# TG21_TX_Xu_ly_ma_tran_phim.net
KiCad netlist of a schematic drawn in Altium Designer
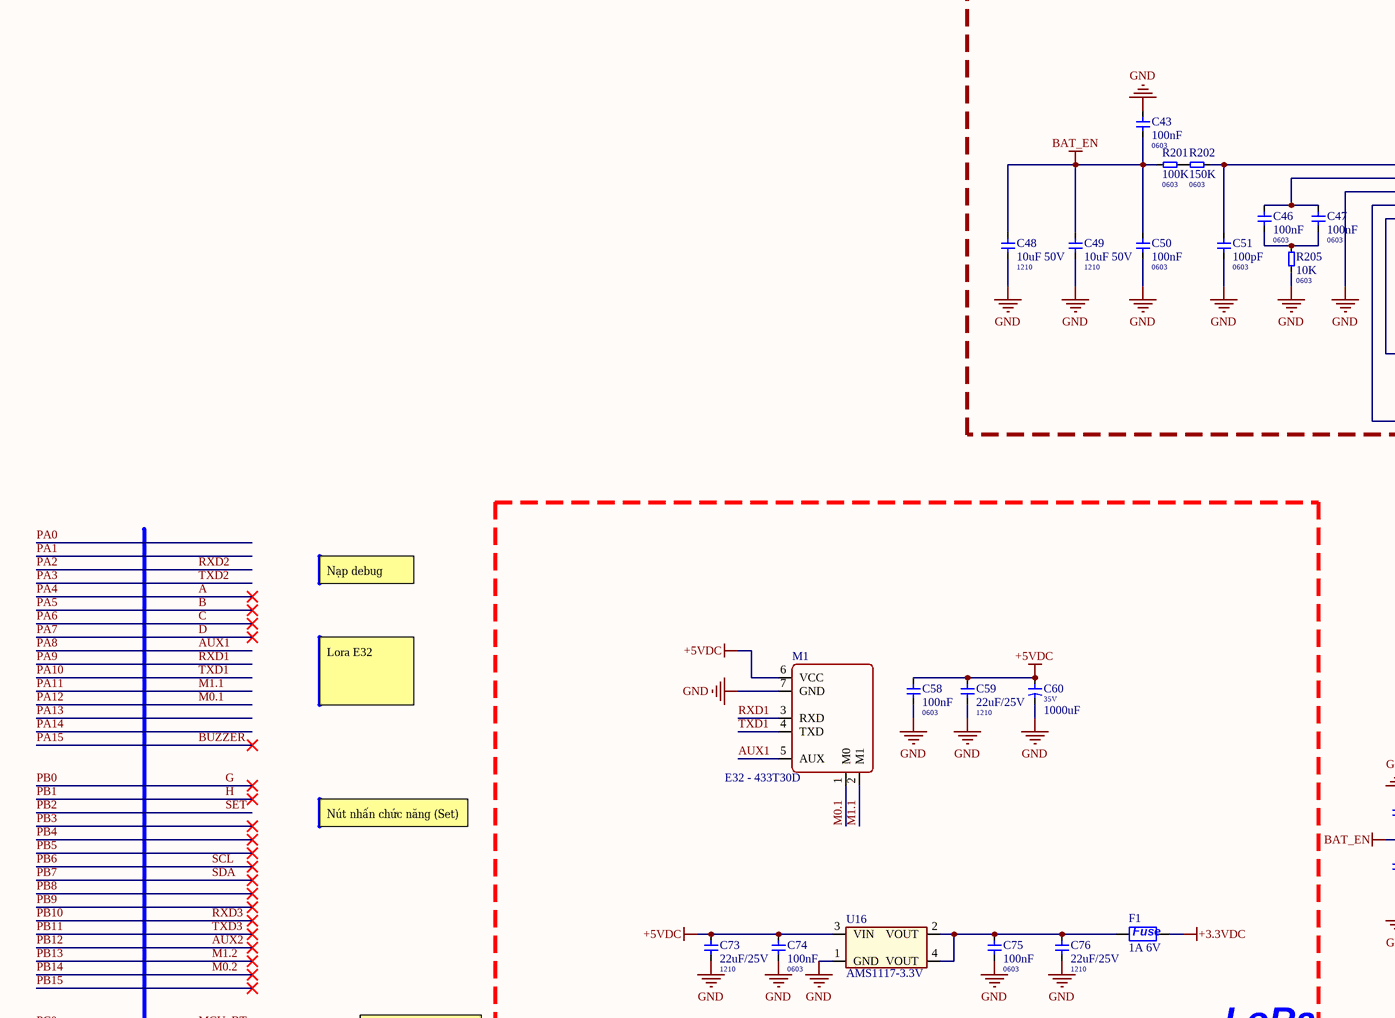
[diagram p0: TG21_TX_Xu ly ma tran phim.SchDoc, top left]
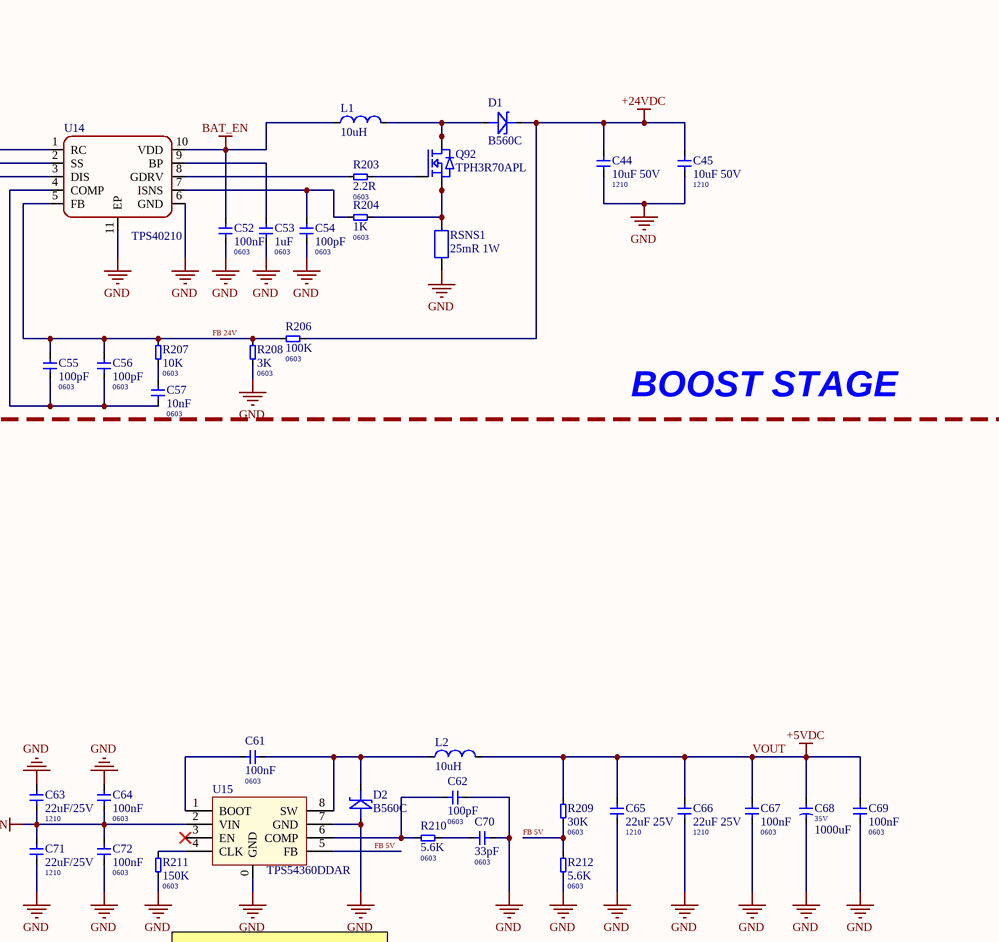
[diagram p1: TG21_TX_Xu ly ma tran phim.SchDoc, top right]
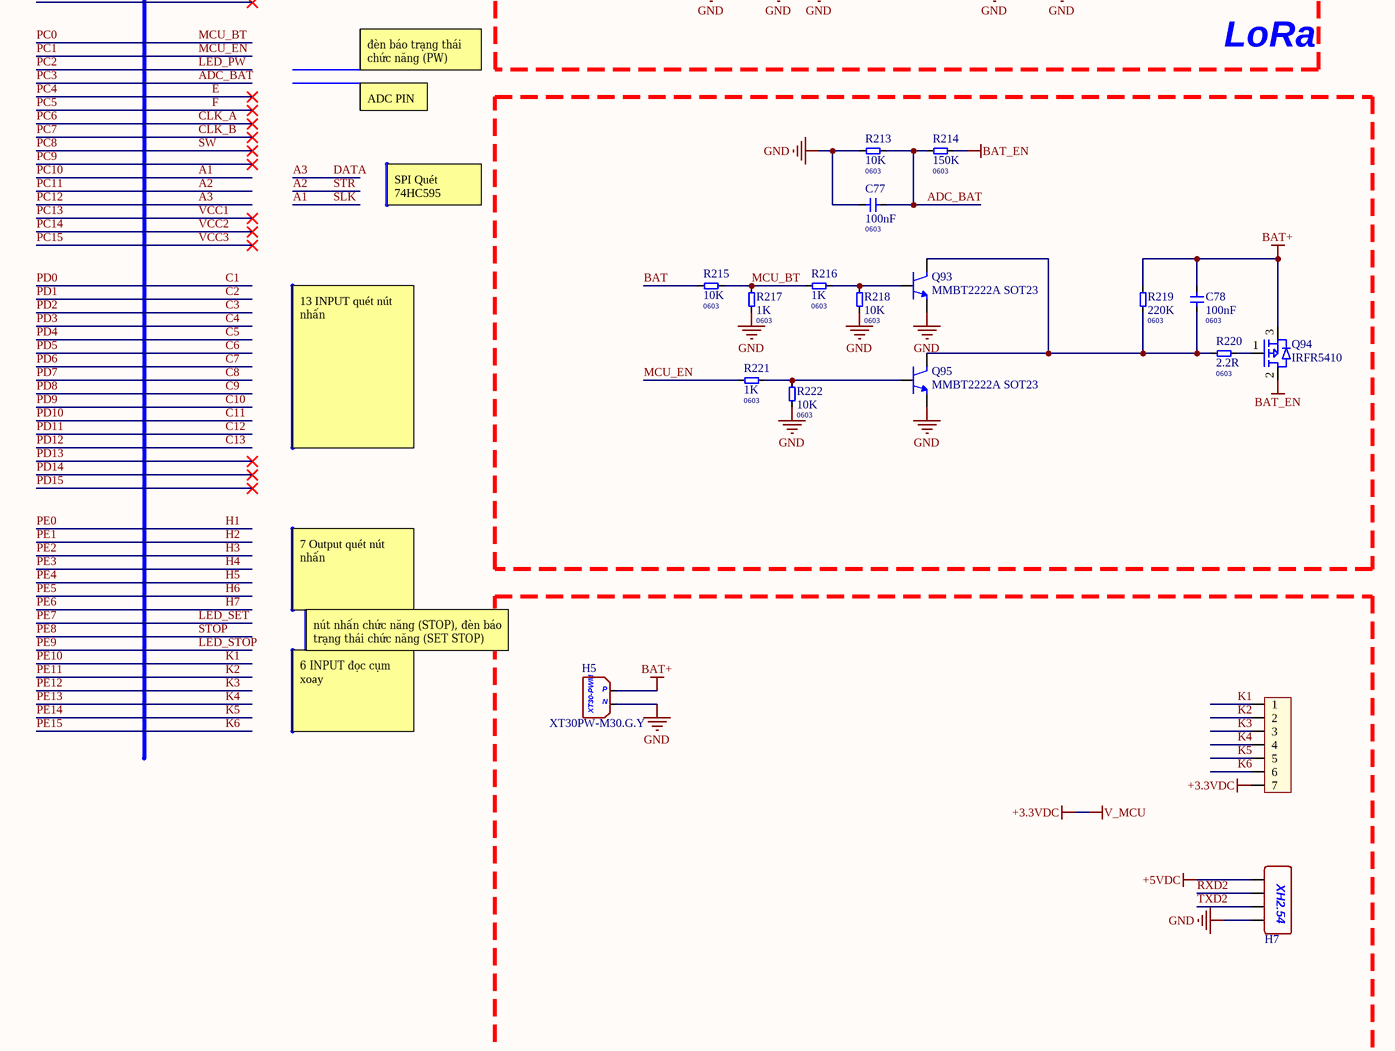
[diagram p2: TG21_TX_Xu ly ma tran phim.SchDoc, bottom left]
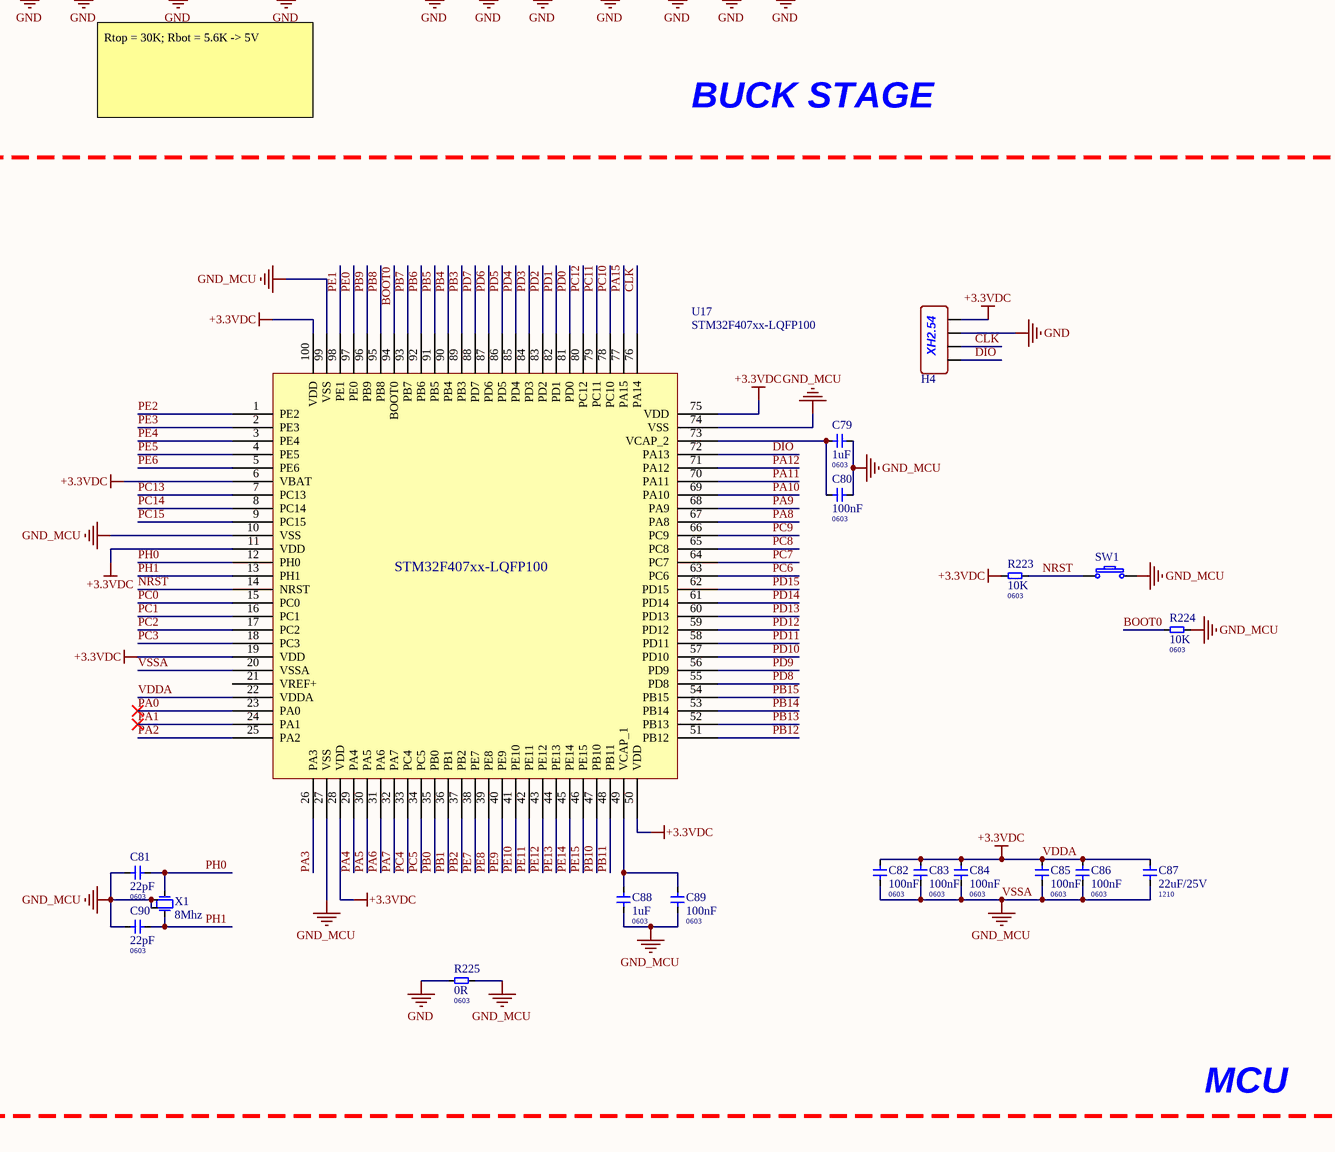
[diagram p3: TG21_TX_Xu ly ma tran phim.SchDoc, bottom right]

(export (version "E")
  (design (tool "Eeschema 10.0.6"))
  (components
    (comp (ref "C43")
      (value "100nF")
      (footprint "0603 MLCC")
      (description "100nF ±10% 50V Ceramic Capacitor X7R 0603")
      (fields
        (field (name "MANUFACTURER") "YAGEO")
        (field (name "MFR. PART #") "CC0603KRX7R9BB104")
        (field (name "PACKAGE") "0603")
      )
      (libsource (lib "TG21_SCHLib") (part "0603 100nF"))
    )
    (comp (ref "C44")
      (value "10uF 50V")
      (footprint "1210 CAPACITOR")
      (description "10uF ±10% 50V Ceramic Capacitor X7R 1210")
      (fields
        (field (name "MANUFACTURER") "Samsung Electro-Mechanics")
        (field (name "MFR. PART #") "CL32B106KBJNNNE")
        (field (name "PACKAGE") "1210")
      )
      (libsource (lib "TG21_SCHLib") (part "1210 10uF 50V"))
    )
    (comp (ref "C45")
      (value "10uF 50V")
      (footprint "1210 CAPACITOR")
      (description "10uF ±10% 50V Ceramic Capacitor X7R 1210")
      (fields
        (field (name "MANUFACTURER") "Samsung Electro-Mechanics")
        (field (name "MFR. PART #") "CL32B106KBJNNNE")
        (field (name "PACKAGE") "1210")
      )
      (libsource (lib "TG21_SCHLib") (part "1210 10uF 50V"))
    )
    (comp (ref "C46")
      (value "100nF")
      (footprint "0603 MLCC")
      (description "100nF ±10% 50V Ceramic Capacitor X7R 0603")
      (fields
        (field (name "MANUFACTURER") "YAGEO")
        (field (name "MFR. PART #") "CC0603KRX7R9BB104")
        (field (name "PACKAGE") "0603")
      )
      (libsource (lib "TG21_SCHLib") (part "0603 100nF"))
    )
    (comp (ref "C47")
      (value "100nF")
      (footprint "0603 MLCC")
      (description "100nF ±10% 50V Ceramic Capacitor X7R 0603")
      (fields
        (field (name "MANUFACTURER") "YAGEO")
        (field (name "MFR. PART #") "CC0603KRX7R9BB104")
        (field (name "PACKAGE") "0603")
      )
      (libsource (lib "TG21_SCHLib") (part "0603 100nF"))
    )
    (comp (ref "C48")
      (value "10uF 50V")
      (footprint "1210 CAPACITOR")
      (description "10uF ±10% 50V Ceramic Capacitor X7R 1210")
      (fields
        (field (name "MANUFACTURER") "Samsung Electro-Mechanics")
        (field (name "MFR. PART #") "CL32B106KBJNNNE")
        (field (name "PACKAGE") "1210")
      )
      (libsource (lib "TG21_SCHLib") (part "1210 10uF 50V"))
    )
    (comp (ref "C49")
      (value "10uF 50V")
      (footprint "1210 CAPACITOR")
      (description "10uF ±10% 50V Ceramic Capacitor X7R 1210")
      (fields
        (field (name "MANUFACTURER") "Samsung Electro-Mechanics")
        (field (name "MFR. PART #") "CL32B106KBJNNNE")
        (field (name "PACKAGE") "1210")
      )
      (libsource (lib "TG21_SCHLib") (part "1210 10uF 50V"))
    )
    (comp (ref "C50")
      (value "100nF")
      (footprint "0603 MLCC")
      (description "100nF ±10% 50V Ceramic Capacitor X7R 0603")
      (fields
        (field (name "MANUFACTURER") "YAGEO")
        (field (name "MFR. PART #") "CC0603KRX7R9BB104")
        (field (name "PACKAGE") "0603")
      )
      (libsource (lib "TG21_SCHLib") (part "0603 100nF"))
    )
    (comp (ref "C51")
      (value "100pF")
      (footprint "0603 MLCC")
      (description "100pF ±5% 50V Ceramic Capacitor C0G 0603")
      (fields
        (field (name "MANUFACTURER") "Samsung Electro-Mechanics")
        (field (name "MFR. PART #") "CL10C101JB8NNNC")
        (field (name "PACKAGE") "0603")
      )
      (libsource (lib "TG21_SCHLib") (part "0603 100pF"))
    )
    (comp (ref "C52")
      (value "100nF")
      (footprint "0603 MLCC")
      (description "100nF ±10% 50V Ceramic Capacitor X7R 0603")
      (fields
        (field (name "MANUFACTURER") "YAGEO")
        (field (name "MFR. PART #") "CC0603KRX7R9BB104")
        (field (name "PACKAGE") "0603")
      )
      (libsource (lib "TG21_SCHLib") (part "0603 100nF"))
    )
    (comp (ref "C53")
      (value "1uF")
      (footprint "0603 MLCC")
      (description "1uF ±10% 50V Ceramic Capacitor X5R 0603")
      (fields
        (field (name "MANUFACTURER") "Samsung Electro-Mechanics")
        (field (name "MFR. PART #") "CL10A105KB8NNNC")
        (field (name "PACKAGE") "0603")
      )
      (libsource (lib "TG21_SCHLib") (part "0603 1uF"))
    )
    (comp (ref "C54")
      (value "100pF")
      (footprint "0603 MLCC")
      (description "100pF ±5% 50V Ceramic Capacitor C0G 0603")
      (fields
        (field (name "MANUFACTURER") "Samsung Electro-Mechanics")
        (field (name "MFR. PART #") "CL10C101JB8NNNC")
        (field (name "PACKAGE") "0603")
      )
      (libsource (lib "TG21_SCHLib") (part "0603 100pF"))
    )
    (comp (ref "C55")
      (value "100pF")
      (footprint "0603 MLCC")
      (description "100pF ±5% 50V Ceramic Capacitor C0G 0603")
      (fields
        (field (name "MANUFACTURER") "Samsung Electro-Mechanics")
        (field (name "MFR. PART #") "CL10C101JB8NNNC")
        (field (name "PACKAGE") "0603")
      )
      (libsource (lib "TG21_SCHLib") (part "0603 100pF"))
    )
    (comp (ref "C56")
      (value "100pF")
      (footprint "0603 MLCC")
      (description "100pF ±5% 50V Ceramic Capacitor C0G 0603")
      (fields
        (field (name "MANUFACTURER") "Samsung Electro-Mechanics")
        (field (name "MFR. PART #") "CL10C101JB8NNNC")
        (field (name "PACKAGE") "0603")
      )
      (libsource (lib "TG21_SCHLib") (part "0603 100pF"))
    )
    (comp (ref "C57")
      (value "10nF")
      (footprint "0603 MLCC")
      (description "10nF ±10% 50V Ceramic Capacitor X7R 0603")
      (fields
        (field (name "MANUFACTURER") "YAGEO")
        (field (name "MFR. PART #") "CC0603KRX7R9BB103")
        (field (name "PACKAGE") "0603")
      )
      (libsource (lib "TG21_SCHLib") (part "0603 10nF"))
    )
    (comp (ref "C58")
      (value "100nF")
      (footprint "0603 MLCC")
      (description "100nF ±10% 50V Ceramic Capacitor X7R 0603")
      (fields
        (field (name "MANUFACTURER") "YAGEO")
        (field (name "MFR. PART #") "CC0603KRX7R9BB104")
        (field (name "PACKAGE") "0603")
      )
      (libsource (lib "TG21_SCHLib") (part "0603 100nF"))
    )
    (comp (ref "C59")
      (value "22uF/25V")
      (footprint "1210 CAPACITOR")
      (description "22uF ±10% 25V Ceramic Capacitor X7R 1210")
      (fields
        (field (name "MANUFACTURER") "Samsung Electro-Mechanics")
        (field (name "MFR. PART #") "CL32B226KAJNNNE")
        (field (name "PACKAGE") "1210")
      )
      (libsource (lib "TG21_SCHLib") (part "1210 22uF 25V X7R"))
    )
    (comp (ref "C60")
      (value "1000uF/35V")
      (footprint "10x20 5.0 Capacitor")
      (description "1000uF 35V Aluminum Electrolytic Capacitors Through Hole,D10xL20mm 2000hrs@105℃")
      (fields
        (field (name "MANUFACTURER") "Rubycon")
        (field (name "MFR. PART #") "35PX1000MEFC10X20")
        (field (name "VOLTAGE") "35V")
        (field (name "CAPACITOR") "1000uF")
      )
      (libsource (lib "TG21_SCHLib") (part "10x20 1000uF 35V"))
    )
    (comp (ref "C61")
      (value "100nF")
      (footprint "0603 MLCC")
      (description "100nF ±10% 50V Ceramic Capacitor X7R 0603")
      (fields
        (field (name "MANUFACTURER") "YAGEO")
        (field (name "MFR. PART #") "CC0603KRX7R9BB104")
        (field (name "PACKAGE") "0603")
      )
      (libsource (lib "TG21_SCHLib") (part "0603 100nF"))
    )
    (comp (ref "C62")
      (value "100pF")
      (footprint "0603 MLCC")
      (description "100pF ±5% 50V Ceramic Capacitor C0G 0603")
      (fields
        (field (name "MANUFACTURER") "Samsung Electro-Mechanics")
        (field (name "MFR. PART #") "CL10C101JB8NNNC")
        (field (name "PACKAGE") "0603")
      )
      (libsource (lib "TG21_SCHLib") (part "0603 100pF"))
    )
    (comp (ref "C63")
      (value "22uF/25V")
      (footprint "1210 CAPACITOR")
      (description "22uF ±10% 25V Ceramic Capacitor X7R 1210")
      (fields
        (field (name "MANUFACTURER") "Samsung Electro-Mechanics")
        (field (name "MFR. PART #") "CL32B226KAJNNNE")
        (field (name "PACKAGE") "1210")
      )
      (libsource (lib "TG21_SCHLib") (part "1210 22uF 25V X7R"))
    )
    (comp (ref "C64")
      (value "100nF")
      (footprint "0603 MLCC")
      (description "100nF ±10% 50V Ceramic Capacitor X7R 0603")
      (fields
        (field (name "MANUFACTURER") "YAGEO")
        (field (name "MFR. PART #") "CC0603KRX7R9BB104")
        (field (name "PACKAGE") "0603")
      )
      (libsource (lib "TG21_SCHLib") (part "0603 100nF"))
    )
    (comp (ref "C65")
      (value "22uF 25V")
      (footprint "1210 CAPACITOR")
      (description "22uF ±10% 25V Ceramic Capacitor X7R 1210")
      (fields
        (field (name "MANUFACTURER") "Samsung Electro-Mechanics")
        (field (name "MFR. PART #") "CL32B226KAJNNNE")
        (field (name "PACKAGE") "1210")
      )
      (libsource (lib "TG21_SCHLib") (part "1210 22uF 25V"))
    )
    (comp (ref "C66")
      (value "22uF 25V")
      (footprint "1210 CAPACITOR")
      (description "22uF ±10% 25V Ceramic Capacitor X7R 1210")
      (fields
        (field (name "MANUFACTURER") "Samsung Electro-Mechanics")
        (field (name "MFR. PART #") "CL32B226KAJNNNE")
        (field (name "PACKAGE") "1210")
      )
      (libsource (lib "TG21_SCHLib") (part "1210 22uF 25V"))
    )
    (comp (ref "C67")
      (value "100nF")
      (footprint "0603 MLCC")
      (description "100nF ±10% 50V Ceramic Capacitor X7R 0603")
      (fields
        (field (name "MANUFACTURER") "YAGEO")
        (field (name "MFR. PART #") "CC0603KRX7R9BB104")
        (field (name "PACKAGE") "0603")
      )
      (libsource (lib "TG21_SCHLib") (part "0603 100nF"))
    )
    (comp (ref "C68")
      (value "1000uF/35V")
      (footprint "10x20 5.0 Capacitor")
      (description "1000uF 35V Aluminum Electrolytic Capacitors Through Hole,D10xL20mm 2000hrs@105℃")
      (fields
        (field (name "MANUFACTURER") "Rubycon")
        (field (name "MFR. PART #") "35PX1000MEFC10X20")
        (field (name "VOLTAGE") "35V")
        (field (name "CAPACITOR") "1000uF")
      )
      (libsource (lib "TG21_SCHLib") (part "10x20 1000uF 35V"))
    )
    (comp (ref "C69")
      (value "100nF")
      (footprint "0603 MLCC")
      (description "100nF ±10% 50V Ceramic Capacitor X7R 0603")
      (fields
        (field (name "MANUFACTURER") "YAGEO")
        (field (name "MFR. PART #") "CC0603KRX7R9BB104")
        (field (name "PACKAGE") "0603")
      )
      (libsource (lib "TG21_SCHLib") (part "0603 100nF"))
    )
    (comp (ref "C70")
      (value "33pF")
      (footprint "0603 MLCC")
      (description "33pF ±5% 50V Ceramic Capacitor NP0 0603")
      (fields
        (field (name "MANUFACTURER") "YAGEO")
        (field (name "MFR. PART #") "CC0603JRNPO9BN330")
        (field (name "PACKAGE") "0603")
      )
      (libsource (lib "TG21_SCHLib") (part "0603 33pF"))
    )
    (comp (ref "C71")
      (value "22uF/25V")
      (footprint "1210 CAPACITOR")
      (description "22uF ±10% 25V Ceramic Capacitor X7R 1210")
      (fields
        (field (name "MANUFACTURER") "Samsung Electro-Mechanics")
        (field (name "MFR. PART #") "CL32B226KAJNNNE")
        (field (name "PACKAGE") "1210")
      )
      (libsource (lib "TG21_SCHLib") (part "1210 22uF 25V X7R"))
    )
    (comp (ref "C72")
      (value "100nF")
      (footprint "0603 MLCC")
      (description "100nF ±10% 50V Ceramic Capacitor X7R 0603")
      (fields
        (field (name "MANUFACTURER") "YAGEO")
        (field (name "MFR. PART #") "CC0603KRX7R9BB104")
        (field (name "PACKAGE") "0603")
      )
      (libsource (lib "TG21_SCHLib") (part "0603 100nF"))
    )
    (comp (ref "C73")
      (value "22uF/25V")
      (footprint "1210 CAPACITOR")
      (description "22uF ±10% 25V Ceramic Capacitor X7R 1210")
      (fields
        (field (name "MANUFACTURER") "Samsung Electro-Mechanics")
        (field (name "MFR. PART #") "CL32B226KAJNNNE")
        (field (name "PACKAGE") "1210")
      )
      (libsource (lib "TG21_SCHLib") (part "1210 22uF 25V X7R"))
    )
    (comp (ref "C74")
      (value "100nF")
      (footprint "0603 MLCC")
      (description "100nF ±10% 50V Ceramic Capacitor X7R 0603")
      (fields
        (field (name "MANUFACTURER") "YAGEO")
        (field (name "MFR. PART #") "CC0603KRX7R9BB104")
        (field (name "PACKAGE") "0603")
      )
      (libsource (lib "TG21_SCHLib") (part "0603 100nF"))
    )
    (comp (ref "C75")
      (value "100nF")
      (footprint "0603 MLCC")
      (description "100nF ±10% 50V Ceramic Capacitor X7R 0603")
      (fields
        (field (name "MANUFACTURER") "YAGEO")
        (field (name "MFR. PART #") "CC0603KRX7R9BB104")
        (field (name "PACKAGE") "0603")
      )
      (libsource (lib "TG21_SCHLib") (part "0603 100nF"))
    )
    (comp (ref "C76")
      (value "22uF/25V")
      (footprint "1210 CAPACITOR")
      (description "22uF ±10% 25V Ceramic Capacitor X7R 1210")
      (fields
        (field (name "MANUFACTURER") "Samsung Electro-Mechanics")
        (field (name "MFR. PART #") "CL32B226KAJNNNE")
        (field (name "PACKAGE") "1210")
      )
      (libsource (lib "TG21_SCHLib") (part "1210 22uF 25V X7R"))
    )
    (comp (ref "C77")
      (value "100nF")
      (footprint "0603 MLCC")
      (description "100nF ±10% 50V Ceramic Capacitor X7R 0603")
      (fields
        (field (name "MANUFACTURER") "YAGEO")
        (field (name "MFR. PART #") "CC0603KRX7R9BB104")
        (field (name "PACKAGE") "0603")
      )
      (libsource (lib "TG21_SCHLib") (part "0603 100nF"))
    )
    (comp (ref "C78")
      (value "100nF")
      (footprint "0603 MLCC")
      (description "100nF ±10% 50V Ceramic Capacitor X7R 0603")
      (fields
        (field (name "MANUFACTURER") "YAGEO")
        (field (name "MFR. PART #") "CC0603KRX7R9BB104")
        (field (name "PACKAGE") "0603")
      )
      (libsource (lib "TG21_SCHLib") (part "0603 100nF"))
    )
    (comp (ref "C79")
      (value "1uF")
      (footprint "0603 MLCC")
      (description "1uF ±10% 50V Ceramic Capacitor X5R 0603")
      (fields
        (field (name "MANUFACTURER") "Samsung Electro-Mechanics")
        (field (name "MFR. PART #") "CL10A105KB8NNNC")
        (field (name "PACKAGE") "0603")
      )
      (libsource (lib "TG21_SCHLib") (part "0603 1uF"))
    )
    (comp (ref "C80")
      (value "100nF")
      (footprint "0603 MLCC")
      (description "100nF ±10% 50V Ceramic Capacitor X7R 0603")
      (fields
        (field (name "MANUFACTURER") "YAGEO")
        (field (name "MFR. PART #") "CC0603KRX7R9BB104")
        (field (name "PACKAGE") "0603")
      )
      (libsource (lib "TG21_SCHLib") (part "0603 100nF"))
    )
    (comp (ref "C81")
      (value "22pF")
      (footprint "0603 MLCC")
      (description "22pF ±5% 50V Ceramic Capacitor C0G 0603")
      (fields
        (field (name "MANUFACTURER") "Samsung Electro-Mechanics")
        (field (name "MFR. PART #") "CL10C220JB8NNNC")
        (field (name "PACKAGE") "0603")
      )
      (libsource (lib "TG21_SCHLib") (part "0603 22pF"))
    )
    (comp (ref "C82")
      (value "100nF")
      (footprint "0603 MLCC")
      (description "100nF ±10% 50V Ceramic Capacitor X7R 0603")
      (fields
        (field (name "MANUFACTURER") "YAGEO")
        (field (name "MFR. PART #") "CC0603KRX7R9BB104")
        (field (name "PACKAGE") "0603")
      )
      (libsource (lib "TG21_SCHLib") (part "0603 100nF"))
    )
    (comp (ref "C83")
      (value "100nF")
      (footprint "0603 MLCC")
      (description "100nF ±10% 50V Ceramic Capacitor X7R 0603")
      (fields
        (field (name "MANUFACTURER") "YAGEO")
        (field (name "MFR. PART #") "CC0603KRX7R9BB104")
        (field (name "PACKAGE") "0603")
      )
      (libsource (lib "TG21_SCHLib") (part "0603 100nF"))
    )
    (comp (ref "C84")
      (value "100nF")
      (footprint "0603 MLCC")
      (description "100nF ±10% 50V Ceramic Capacitor X7R 0603")
      (fields
        (field (name "MANUFACTURER") "YAGEO")
        (field (name "MFR. PART #") "CC0603KRX7R9BB104")
        (field (name "PACKAGE") "0603")
      )
      (libsource (lib "TG21_SCHLib") (part "0603 100nF"))
    )
    (comp (ref "C85")
      (value "100nF")
      (footprint "0603 MLCC")
      (description "100nF ±10% 50V Ceramic Capacitor X7R 0603")
      (fields
        (field (name "MANUFACTURER") "YAGEO")
        (field (name "MFR. PART #") "CC0603KRX7R9BB104")
        (field (name "PACKAGE") "0603")
      )
      (libsource (lib "TG21_SCHLib") (part "0603 100nF"))
    )
    (comp (ref "C86")
      (value "100nF")
      (footprint "0603 MLCC")
      (description "100nF ±10% 50V Ceramic Capacitor X7R 0603")
      (fields
        (field (name "MANUFACTURER") "YAGEO")
        (field (name "MFR. PART #") "CC0603KRX7R9BB104")
        (field (name "PACKAGE") "0603")
      )
      (libsource (lib "TG21_SCHLib") (part "0603 100nF"))
    )
    (comp (ref "C87")
      (value "22uF/25V")
      (footprint "1210 CAPACITOR")
      (description "22uF ±10% 25V Ceramic Capacitor X7R 1210")
      (fields
        (field (name "MANUFACTURER") "Samsung Electro-Mechanics")
        (field (name "MFR. PART #") "CL32B226KAJNNNE")
        (field (name "PACKAGE") "1210")
      )
      (libsource (lib "TG21_SCHLib") (part "1210 22uF 25V X7R"))
    )
    (comp (ref "C88")
      (value "1uF")
      (footprint "0603 MLCC")
      (description "1uF ±10% 50V Ceramic Capacitor X5R 0603")
      (fields
        (field (name "MANUFACTURER") "Samsung Electro-Mechanics")
        (field (name "MFR. PART #") "CL10A105KB8NNNC")
        (field (name "PACKAGE") "0603")
      )
      (libsource (lib "TG21_SCHLib") (part "0603 1uF"))
    )
    (comp (ref "C89")
      (value "100nF")
      (footprint "0603 MLCC")
      (description "100nF ±10% 50V Ceramic Capacitor X7R 0603")
      (fields
        (field (name "MANUFACTURER") "YAGEO")
        (field (name "MFR. PART #") "CC0603KRX7R9BB104")
        (field (name "PACKAGE") "0603")
      )
      (libsource (lib "TG21_SCHLib") (part "0603 100nF"))
    )
    (comp (ref "C90")
      (value "22pF")
      (footprint "0603 MLCC")
      (description "22pF ±5% 50V Ceramic Capacitor C0G 0603")
      (fields
        (field (name "MANUFACTURER") "Samsung Electro-Mechanics")
        (field (name "MFR. PART #") "CL10C220JB8NNNC")
        (field (name "PACKAGE") "0603")
      )
      (libsource (lib "TG21_SCHLib") (part "0603 22pF"))
    )
    (comp (ref "D1")
      (value "B560C")
      (footprint "SMC(DO-214AB)")
      (description "Voltage： 60V Current： 5A")
      (fields (field (name "MANUFACTURER") "DIODES") (field (name "MFR. PART #") "B560C-13-F"))
      (libsource (lib "TG21_SCHLib") (part "B560C - 13- F"))
    )
    (comp (ref "D2")
      (value "B560C")
      (footprint "SMC(DO-214AB)")
      (description "Voltage： 60V Current： 5A")
      (fields (field (name "MANUFACTURER") "DIODES") (field (name "MFR. PART #") "B560C-13-F"))
      (libsource (lib "TG21_SCHLib") (part "B560C - 13- F"))
    )
    (comp (ref "F1")
      (value "1A 6V")
      (footprint "1206 - Fuse")
      (description "Polymeric PTC Resettable Fuse 6V 1A Surface Mount 1206")
      (fields (field (name "MANUFACTURER") "BHFUSE") (field (name "MFR. PART #") "BSMD1206-100-6V"))
      (libsource (lib "TG21_SCHLib") (part "1206 Fuse 1A 6V"))
    )
    (comp (ref "H4")
      (value "XY-XH2.54-4PZZ")
      (footprint "XH2.54 - 4PZZ")
      (description "XH 1 4P -25℃~+85℃ 2.54mm 4 2A 250V 1x4P Through Hole,P=2.54mm Headers, Male Pins RoHS")
      (fields (field (name "MANUFACTURER") "XYECONN") (field (name "LCSC PART #") "C53201003"))
      (libsource (lib "TG21_SCHLib") (part "XH2.54 4PZZ"))
    )
    (comp (ref "H5")
      (value "XT30PW-M30.G.Y")
      (footprint "XT30")
      (description "AMASS XT30PW-M30.G.Y")
      (fields (field (name "LCSC PART #") "C431092") (field (name "MANUFACTURER") "Changzhou Amass Elec"))
      (libsource (lib "TG21_SCHLib") (part "XT30PW-M30.G.Y"))
    )
    (comp (ref "H6")
      (value "Header 7P 2.54 Duc Thang")
      (footprint "XH2.54M-7")
      (description "Cắm")
      (libsource (lib "Header") (part "Header 7P 2.54 Duc Thang"))
    )
    (comp (ref "H7")
      (value "XY-XH2.54-4PZZ")
      (footprint "XH2.54 - 4PZZ")
      (description "XH 1 4P -25℃~+85℃ 2.54mm 4 2A 250V 1x4P Through Hole,P=2.54mm Headers, Male Pins RoHS")
      (fields (field (name "MANUFACTURER") "XYECONN") (field (name "LCSC PART #") "C53201003"))
      (libsource (lib "TG21_TX_Ma tran phimPrjPcb") (part "XH2.54 4PZZ"))
    )
    (comp (ref "L1")
      (value "10uH")
      (footprint "12.2x12.2mm")
      (description "5.4A 10uH 21.6mΩ ±20% SMD,12.2x12.2mm Fixed Inductors RoHS")
      (fields (field (name "MANUFACTURER") "MINGSTAR") (field (name "MFR. PART #") "CDRH127N-100M"))
      (libsource (lib "TG21_SCHLib") (part "CDRH127N 10uH"))
    )
    (comp (ref "L2")
      (value "10uH")
      (footprint "12.2x12.2mm")
      (description "5.4A 10uH 21.6mΩ ±20% SMD,12.2x12.2mm Fixed Inductors RoHS")
      (fields (field (name "MANUFACTURER") "MINGSTAR") (field (name "MFR. PART #") "CDRH127N-100M"))
      (libsource (lib "TG21_SCHLib") (part "CDRH127N 10uH"))
    )
    (comp (ref "M1")
      (value "E32 - 433T30D")
      (footprint "E32 - 433T30D")
      (description "8km UART Through Hole RF Transceiver Modules and Modems RoHS")
      (fields (field (name "MANUFACTURER") "EBYTE") (field (name "MFR. PART #") "E32-433T30D"))
      (libsource (lib "TG21_SCHLib") (part "E32 - 433T30D"))
    )
    (comp (ref "Q92")
      (value "TPH3R70APL")
      (footprint "SOP Advanced")
      (fields (field (name "MANUFACTURER") "TOSHIBA") (field (name "LCSC PART #") "C556308"))
      (libsource (lib "TG21_SCHLib") (part "TPH3R70"))
    )
    (comp (ref "Q93")
      (value "MMBT2222A SOT23")
      (footprint "SOT23_HVT")
      (description "Bipolar (BJT) Transistor NPN 20V 350mA 300MHz 300mW Surface Mount SOT-23")
      (fields (field (name "MANUFACTURER") "JSMSEMI") (field (name "MFR. PART #") "MMBT2222A"))
      (libsource (lib "TG21_SCHLib") (part "MMBT2222A"))
    )
    (comp (ref "Q94")
      (value "IRFR5410")
      (footprint "TO - 252")
      (description "P-Channel 100V 13A 66W Surface Mount DPAK(TO-252AA)")
      (fields (field (name "MANUFACTURER") "Infineon") (field (name "MFR. PART #") "IRFR5410TRPBF"))
      (libsource (lib "TG21_SCHLib") (part "IRFR5410TRPBF"))
    )
    (comp (ref "Q95")
      (value "MMBT2222A SOT23")
      (footprint "SOT23_HVT")
      (description "Bipolar (BJT) Transistor NPN 20V 350mA 300MHz 300mW Surface Mount SOT-23")
      (fields (field (name "MANUFACTURER") "JSMSEMI") (field (name "MFR. PART #") "MMBT2222A"))
      (libsource (lib "TG21_SCHLib") (part "MMBT2222A"))
    )
    (comp (ref "R201")
      (value "100K")
      (footprint "0603 Resistors")
      (description "100mW 100KΩ 75V Thick Film Resistor ±1% ±100ppm/℃ 0603 Chip Resistor - Surface Mount RoHS")
      (fields
        (field (name "MFR. PART #") "FRC0603F1003TS")
        (field (name "LCSC PART #") "C2906980")
        (field (name "PACKAGE") "0603")
      )
      (libsource (lib "TG21_SCHLib") (part "0603 100K"))
    )
    (comp (ref "R202")
      (value "150K")
      (footprint "0603 Resistors")
      (description "100mW 150KΩ 75V Thick Film Resistor ±1% ±100ppm/℃ 0603 Chip Resistor - Surface Mount RoHS")
      (fields
        (field (name "MFR. PART #") "0603WAF1503T5E")
        (field (name "LCSC PART #") "C22807")
        (field (name "PACKAGE") "0603")
      )
      (libsource (lib "TG21_SCHLib") (part "0603 150K"))
    )
    (comp (ref "R203")
      (value "2.2R")
      (footprint "0603 Resistors")
      (description "100mW 2.2Ω 75V Thick Film Resistor ±1% ±100ppm/℃ 0603 Chip Resistor - Surface Mount RoHS")
      (fields
        (field (name "MFR. PART #") "FRC0805F2R20TS")
        (field (name "LCSC PART #") "C2933402")
        (field (name "PACKAGE") "0603")
      )
      (libsource (lib "TG21_SCHLib") (part "0603 2.2R"))
    )
    (comp (ref "R204")
      (value "1K")
      (footprint "0603 Resistors")
      (description "100mW 1kΩ 75V Thick Film Resistor ±1% ±100ppm/℃ 0603 Chip Resistor - Surface Mount RoHS")
      (fields
        (field (name "MFR. PART #") "CRCW06031K00FKEA")
        (field (name "LCSC PART #") "C844920")
        (field (name "PACKAGE") "0603")
      )
      (libsource (lib "TG21_SCHLib") (part "0603 1K"))
    )
    (comp (ref "R205")
      (value "10K")
      (footprint "0603 Resistors")
      (description "100mW 10kΩ 75V Thick Film Resistor ±1% ±100ppm/℃ 0603 Chip Resistor - Surface Mount RoHS")
      (fields
        (field (name "MANUFACTURER") "VISHAY")
        (field (name "MFR. PART #") "CRCW060310K0FKEA")
        (field (name "PACKAGE") "0603")
      )
      (libsource (lib "TG21_SCHLib") (part "0603 10K"))
    )
    (comp (ref "R206")
      (value "100K")
      (footprint "0603 Resistors")
      (description "100mW 100KΩ 75V Thick Film Resistor ±1% ±100ppm/℃ 0603 Chip Resistor - Surface Mount RoHS")
      (fields
        (field (name "MFR. PART #") "FRC0603F1003TS")
        (field (name "LCSC PART #") "C2906980")
        (field (name "PACKAGE") "0603")
      )
      (libsource (lib "TG21_SCHLib") (part "0603 100K"))
    )
    (comp (ref "R207")
      (value "10K")
      (footprint "0603 Resistors")
      (description "100mW 10kΩ 75V Thick Film Resistor ±1% ±100ppm/℃ 0603 Chip Resistor - Surface Mount RoHS")
      (fields
        (field (name "MANUFACTURER") "VISHAY")
        (field (name "MFR. PART #") "CRCW060310K0FKEA")
        (field (name "PACKAGE") "0603")
      )
      (libsource (lib "TG21_SCHLib") (part "0603 10K"))
    )
    (comp (ref "R208")
      (value "3K")
      (footprint "0603 Resistors")
      (description "3kΩ ±1% 100mW 0603 Thick Film Resistor")
      (fields
        (field (name "MFR. PART #") "0805W8F7503T5E")
        (field (name "LCSC PART #") "C17817")
        (field (name "PACKAGE") "0603")
      )
      (libsource (lib "TG21_SCHLib") (part "0603 3K"))
    )
    (comp (ref "R209")
      (value "30K")
      (footprint "0603 Resistors")
      (description "30kΩ ±1% 100mW 0603 Thick Film Resistor")
      (fields
        (field (name "MFR. PART #") "FRC0603F3002TS")
        (field (name "LCSC PART #") "C2907025")
        (field (name "PACKAGE") "0603")
      )
      (libsource (lib "TG21_SCHLib") (part "0603 30K"))
    )
    (comp (ref "R210")
      (value "5.6K")
      (footprint "0603 Resistors")
      (description "100mW 5.6KΩ 75V Thick Film Resistor ±1% ±100ppm/℃ 0603 Chip Resistor - Surface Mount RoHS")
      (fields
        (field (name "MFR. PART #") "FRC0603F5601TS")
        (field (name "LCSC PART #") "C2907046")
        (field (name "PACKAGE") "0603")
      )
      (libsource (lib "TG21_SCHLib") (part "0603 5.6K"))
    )
    (comp (ref "R211")
      (value "150K")
      (footprint "0603 Resistors")
      (description "100mW 150KΩ 75V Thick Film Resistor ±1% ±100ppm/℃ 0603 Chip Resistor - Surface Mount RoHS")
      (fields
        (field (name "MFR. PART #") "0603WAF1503T5E")
        (field (name "LCSC PART #") "C22807")
        (field (name "PACKAGE") "0603")
      )
      (libsource (lib "TG21_SCHLib") (part "0603 150K"))
    )
    (comp (ref "R212")
      (value "5.6K")
      (footprint "0603 Resistors")
      (description "100mW 5.6KΩ 75V Thick Film Resistor ±1% ±100ppm/℃ 0603 Chip Resistor - Surface Mount RoHS")
      (fields
        (field (name "MFR. PART #") "FRC0603F5601TS")
        (field (name "LCSC PART #") "C2907046")
        (field (name "PACKAGE") "0603")
      )
      (libsource (lib "TG21_SCHLib") (part "0603 5.6K"))
    )
    (comp (ref "R213")
      (value "10K")
      (footprint "0603 Resistors")
      (description "100mW 10kΩ 75V Thick Film Resistor ±1% ±100ppm/℃ 0603 Chip Resistor - Surface Mount RoHS")
      (fields
        (field (name "MANUFACTURER") "VISHAY")
        (field (name "MFR. PART #") "CRCW060310K0FKEA")
        (field (name "PACKAGE") "0603")
      )
      (libsource (lib "TG21_SCHLib") (part "0603 10K"))
    )
    (comp (ref "R214")
      (value "150K")
      (footprint "0603 Resistors")
      (description "100mW 150KΩ 75V Thick Film Resistor ±1% ±100ppm/℃ 0603 Chip Resistor - Surface Mount RoHS")
      (fields
        (field (name "MFR. PART #") "0603WAF1503T5E")
        (field (name "LCSC PART #") "C22807")
        (field (name "PACKAGE") "0603")
      )
      (libsource (lib "TG21_SCHLib") (part "0603 150K"))
    )
    (comp (ref "R215")
      (value "10K")
      (footprint "0603 Resistors")
      (description "100mW 10kΩ 75V Thick Film Resistor ±1% ±100ppm/℃ 0603 Chip Resistor - Surface Mount RoHS")
      (fields
        (field (name "MANUFACTURER") "VISHAY")
        (field (name "MFR. PART #") "CRCW060310K0FKEA")
        (field (name "PACKAGE") "0603")
      )
      (libsource (lib "TG21_SCHLib") (part "0603 10K"))
    )
    (comp (ref "R216")
      (value "1K")
      (footprint "0603 Resistors")
      (description "100mW 1kΩ 75V Thick Film Resistor ±1% ±100ppm/℃ 0603 Chip Resistor - Surface Mount RoHS")
      (fields
        (field (name "MFR. PART #") "CRCW06031K00FKEA")
        (field (name "LCSC PART #") "C844920")
        (field (name "PACKAGE") "0603")
      )
      (libsource (lib "TG21_SCHLib") (part "0603 1K"))
    )
    (comp (ref "R217")
      (value "1K")
      (footprint "0603 Resistors")
      (description "100mW 1kΩ 75V Thick Film Resistor ±1% ±100ppm/℃ 0603 Chip Resistor - Surface Mount RoHS")
      (fields
        (field (name "MFR. PART #") "CRCW06031K00FKEA")
        (field (name "LCSC PART #") "C844920")
        (field (name "PACKAGE") "0603")
      )
      (libsource (lib "TG21_SCHLib") (part "0603 1K"))
    )
    (comp (ref "R218")
      (value "10K")
      (footprint "0603 Resistors")
      (description "100mW 10kΩ 75V Thick Film Resistor ±1% ±100ppm/℃ 0603 Chip Resistor - Surface Mount RoHS")
      (fields
        (field (name "MANUFACTURER") "VISHAY")
        (field (name "MFR. PART #") "CRCW060310K0FKEA")
        (field (name "PACKAGE") "0603")
      )
      (libsource (lib "TG21_SCHLib") (part "0603 10K"))
    )
    (comp (ref "R219")
      (value "220K")
      (footprint "0603 Resistors")
      (description "100mW 220KΩ 75V Thick Film Resistor ±1% ±100ppm/℃ 0603 Chip Resistor - Surface Mount RoHS")
      (fields
        (field (name "MFR. PART #") "FRC0603F2203TS")
        (field (name "LCSC PART #") "C2907013")
        (field (name "PACKAGE") "0603")
      )
      (libsource (lib "TG21_SCHLib") (part "0603 220K"))
    )
    (comp (ref "R220")
      (value "2.2R")
      (footprint "0603 Resistors")
      (description "100mW 2.2Ω 75V Thick Film Resistor ±1% ±100ppm/℃ 0603 Chip Resistor - Surface Mount RoHS")
      (fields
        (field (name "MFR. PART #") "FRC0805F2R20TS")
        (field (name "LCSC PART #") "C2933402")
        (field (name "PACKAGE") "0603")
      )
      (libsource (lib "TG21_SCHLib") (part "0603 2.2R"))
    )
    (comp (ref "R221")
      (value "1K")
      (footprint "0603 Resistors")
      (description "100mW 1kΩ 75V Thick Film Resistor ±1% ±100ppm/℃ 0603 Chip Resistor - Surface Mount RoHS")
      (fields
        (field (name "MFR. PART #") "CRCW06031K00FKEA")
        (field (name "LCSC PART #") "C844920")
        (field (name "PACKAGE") "0603")
      )
      (libsource (lib "TG21_SCHLib") (part "0603 1K"))
    )
    (comp (ref "R222")
      (value "10K")
      (footprint "0603 Resistors")
      (description "100mW 10kΩ 75V Thick Film Resistor ±1% ±100ppm/℃ 0603 Chip Resistor - Surface Mount RoHS")
      (fields
        (field (name "MANUFACTURER") "VISHAY")
        (field (name "MFR. PART #") "CRCW060310K0FKEA")
        (field (name "PACKAGE") "0603")
      )
      (libsource (lib "TG21_SCHLib") (part "0603 10K"))
    )
    (comp (ref "R223")
      (value "10K")
      (footprint "0603 Resistors")
      (description "100mW 10kΩ 75V Thick Film Resistor ±1% ±100ppm/℃ 0603 Chip Resistor - Surface Mount RoHS")
      (fields
        (field (name "MANUFACTURER") "VISHAY")
        (field (name "MFR. PART #") "CRCW060310K0FKEA")
        (field (name "PACKAGE") "0603")
      )
      (libsource (lib "TG21_SCHLib") (part "0603 10K"))
    )
    (comp (ref "R224")
      (value "10K")
      (footprint "0603 Resistors")
      (description "100mW 10kΩ 75V Thick Film Resistor ±1% ±100ppm/℃ 0603 Chip Resistor - Surface Mount RoHS")
      (fields
        (field (name "MANUFACTURER") "VISHAY")
        (field (name "MFR. PART #") "CRCW060310K0FKEA")
        (field (name "PACKAGE") "0603")
      )
      (libsource (lib "TG21_SCHLib") (part "0603 10K"))
    )
    (comp (ref "R225")
      (value "0R")
      (footprint "0603 Resistors")
      (description "100mW 0Ω 75V Thick Film Resistor ±1% ±100ppm/℃ 0603 Chip Resistor - Surface Mount RoHS")
      (fields
        (field (name "MFR. PART #") "RC0603FR-070RL")
        (field (name "LCSC PART #") "C100044")
        (field (name "PACKAGE") "0603")
      )
      (libsource (lib "TG21_SCHLib") (part "0603 0R"))
    )
    (comp (ref "RSNS1")
      (value "25mR 1W")
      (footprint "1206 Resistor")
      (description "1W 25mΩ ±50ppm/℃ ±1% 1206 Chip Resistor - Surface Mount RoHS")
      (fields (field (name "MANUFACTURER") "JIERR") (field (name "MFR. PART #") "JER1206F1R025"))
      (libsource (lib "TG21_SCHLib") (part "1206 25mR"))
    )
    (comp (ref "SW1")
      (value "HX 3x6x2.5A-2.5N")
      (footprint "SW - 2P SMD")
      (description "Tactile Switch SPST 250gf 2.5mm SMD (SMT) Tab 6mm x 3.6mm Surface Mount")
      (fields (field (name "MANUFACTURER") "hanxia") (field (name "LCSC PART #") "C36498960"))
      (libsource (lib "TG21_SCHLib") (part "Switch Tactile 3x6x2.5"))
    )
    (comp (ref "U14")
      (value "TPS40210")
      (footprint "MSOP 10")
      (description "1 MSOP-10-EP DC DC Switching Controllers RoHS")
      (fields (field (name "MANUFACTURER") "TI") (field (name "MFR. PART #") "TPS40210DGQR"))
      (libsource (lib "TG21_SCHLib") (part "TPS40210DGQR"))
    )
    (comp (ref "U15")
      (value "TPS54360DDAR")
      (footprint "SOIC8")
      (description "60V Input, 3.5A Output Step-Down DC-DC Converter")
      (fields (field (name "MANUFACTURER") "TI") (field (name "LCSC PART #") "C44377"))
      (libsource (lib "TG21_SCHLib") (part "TPS54360"))
    )
    (comp (ref "U16")
      (value "AMS1117-3.3V")
      (footprint "SOT223 - 4P")
      (libsource (lib "TG21_SCHLib") (part "AMS1117"))
    )
    (comp (ref "U17")
      (value "STM32F407xx-LQFP100")
      (footprint "STM32_LQFP100")
      (libsource (lib "TG21_TX_Xu ly ma tran phim") (part "STM32F407xx-LQFP100"))
    )
    (comp (ref "X1")
      (value "8Mhz")
      (footprint "5032 4P")
      (description "Crystal 8MHz ±20ppm 12pF SMD5032-4P")
      (fields (field (name "MANUFACTURER") "SOSET") (field (name "MFR. PART #") "5032 8M 12PF 20PPM 4P"))
      (libsource (lib "TG21_SCHLib") (part "Crystal 5032 4P 8MhZ"))
    )
  )
  (nets
    (net (code "1") (name "+3.3VDC") (class "Default")
      (node (ref "C82") (pin "2") (pinfunction "2_2") (pintype "passive"))
      (node (ref "C83") (pin "2") (pinfunction "2_2") (pintype "passive"))
      (node (ref "C84") (pin "2") (pinfunction "2_2") (pintype "passive"))
      (node (ref "C85") (pin "2") (pinfunction "2_2") (pintype "passive"))
      (node (ref "C86") (pin "2") (pinfunction "2_2") (pintype "passive"))
      (node (ref "C87") (pin "1") (pinfunction "1_1") (pintype "passive"))
      (node (ref "F1") (pin "2") (pinfunction "2_2") (pintype "passive"))
      (node (ref "H4") (pin "1") (pinfunction "1_1") (pintype "passive"))
      (node (ref "H6") (pin "7") (pinfunction "7_7") (pintype "passive"))
      (node (ref "R223") (pin "1") (pinfunction "1_1") (pintype "passive"))
      (node (ref "U17") (pin "100") (pinfunction "VDD_100") (pintype "passive"))
      (node (ref "U17") (pin "11") (pinfunction "VDD_11") (pintype "passive"))
      (node (ref "U17") (pin "19") (pinfunction "VDD_19") (pintype "passive"))
      (node (ref "U17") (pin "22") (pinfunction "VDDA_22") (pintype "passive"))
      (node (ref "U17") (pin "28") (pinfunction "VDD_28") (pintype "passive"))
      (node (ref "U17") (pin "50") (pinfunction "VDD_50") (pintype "passive"))
      (node (ref "U17") (pin "6") (pinfunction "VBAT_6") (pintype "passive"))
      (node (ref "U17") (pin "75") (pinfunction "VDD_75") (pintype "passive"))
    )
    (net (code "2") (name "+5VDC") (class "Default")
      (node (ref "C58") (pin "2") (pinfunction "2_2") (pintype "passive"))
      (node (ref "C59") (pin "2") (pinfunction "2_2") (pintype "passive"))
      (node (ref "C60") (pin "1") (pinfunction "1_1") (pintype "passive"))
      (node (ref "C65") (pin "2") (pinfunction "2_2") (pintype "passive"))
      (node (ref "C66") (pin "2") (pinfunction "2_2") (pintype "passive"))
      (node (ref "C67") (pin "2") (pinfunction "2_2") (pintype "passive"))
      (node (ref "C68") (pin "1") (pinfunction "1_1") (pintype "passive"))
      (node (ref "C69") (pin "2") (pinfunction "2_2") (pintype "passive"))
      (node (ref "C73") (pin "1") (pinfunction "1_1") (pintype "passive"))
      (node (ref "C74") (pin "2") (pinfunction "2_2") (pintype "passive"))
      (node (ref "H7") (pin "4") (pinfunction "4_4") (pintype "passive"))
      (node (ref "L2") (pin "2") (pinfunction "2_2") (pintype "passive"))
      (node (ref "M1") (pin "6") (pinfunction "VCC_6") (pintype "passive"))
      (node (ref "R209") (pin "2") (pinfunction "2_2") (pintype "passive"))
      (node (ref "U16") (pin "3") (pinfunction "VIN_3") (pintype "passive"))
    )
    (net (code "3") (name "+24VDC") (class "Default")
      (node (ref "C44") (pin "2") (pinfunction "2_2") (pintype "passive"))
      (node (ref "C45") (pin "2") (pinfunction "2_2") (pintype "passive"))
      (node (ref "D1") (pin "2") (pinfunction "Kathode_2") (pintype "passive"))
      (node (ref "R206") (pin "2") (pinfunction "2_2") (pintype "passive"))
    )
    (net (code "4") (name "/A") (class "Default")
      (node (ref "U17") (pin "29") (pinfunction "PA4_29") (pintype "passive"))
    )
    (net (code "5") (name "/A1") (class "Default")
      (node (ref "U17") (pin "78") (pinfunction "PC10_78") (pintype "passive"))
    )
    (net (code "6") (name "/A2") (class "Default")
      (node (ref "U17") (pin "79") (pinfunction "PC11_79") (pintype "passive"))
    )
    (net (code "7") (name "/A3") (class "Default")
      (node (ref "U17") (pin "80") (pinfunction "PC12_80") (pintype "passive"))
    )
    (net (code "8") (name "/ADC_BAT") (class "Default")
      (node (ref "C77") (pin "1") (pinfunction "1_1") (pintype "passive"))
      (node (ref "R213") (pin "1") (pinfunction "1_1") (pintype "passive"))
      (node (ref "R214") (pin "1") (pinfunction "1_1") (pintype "passive"))
      (node (ref "U17") (pin "18") (pinfunction "PC3_18") (pintype "passive"))
    )
    (net (code "9") (name "/AUX1") (class "Default")
      (node (ref "M1") (pin "5") (pinfunction "AUX_5") (pintype "passive"))
      (node (ref "U17") (pin "67") (pinfunction "PA8_67") (pintype "passive"))
    )
    (net (code "10") (name "/AUX2") (class "Default")
      (node (ref "U17") (pin "51") (pinfunction "PB12_51") (pintype "passive"))
    )
    (net (code "11") (name "/B") (class "Default")
      (node (ref "U17") (pin "30") (pinfunction "PA5_30") (pintype "passive"))
    )
    (net (code "12") (name "/BAT") (class "Default")
      (node (ref "R215") (pin "1") (pinfunction "1_1") (pintype "passive"))
    )
    (net (code "13") (name "/BOOT0") (class "Default")
      (node (ref "R224") (pin "2") (pinfunction "2_2") (pintype "passive"))
      (node (ref "U17") (pin "94") (pinfunction "BOOT0_94") (pintype "passive"))
    )
    (net (code "14") (name "/BUZZER") (class "Default")
      (node (ref "U17") (pin "77") (pinfunction "PA15_77") (pintype "passive"))
    )
    (net (code "15") (name "/C") (class "Default")
      (node (ref "U17") (pin "31") (pinfunction "PA6_31") (pintype "passive"))
    )
    (net (code "16") (name "/C1") (class "Default")
      (node (ref "U17") (pin "81") (pinfunction "PD0_81") (pintype "passive"))
    )
    (net (code "17") (name "/C2") (class "Default")
      (node (ref "U17") (pin "82") (pinfunction "PD1_82") (pintype "passive"))
    )
    (net (code "18") (name "/C3") (class "Default")
      (node (ref "U17") (pin "83") (pinfunction "PD2_83") (pintype "passive"))
    )
    (net (code "19") (name "/C4") (class "Default")
      (node (ref "U17") (pin "84") (pinfunction "PD3_84") (pintype "passive"))
    )
    (net (code "20") (name "/C5") (class "Default")
      (node (ref "U17") (pin "85") (pinfunction "PD4_85") (pintype "passive"))
    )
    (net (code "21") (name "/C6") (class "Default")
      (node (ref "U17") (pin "86") (pinfunction "PD5_86") (pintype "passive"))
    )
    (net (code "22") (name "/C7") (class "Default")
      (node (ref "U17") (pin "87") (pinfunction "PD6_87") (pintype "passive"))
    )
    (net (code "23") (name "/C8") (class "Default")
      (node (ref "U17") (pin "88") (pinfunction "PD7_88") (pintype "passive"))
    )
    (net (code "24") (name "/C9") (class "Default")
      (node (ref "U17") (pin "55") (pinfunction "PD8_55") (pintype "passive"))
    )
    (net (code "25") (name "/C10") (class "Default")
      (node (ref "U17") (pin "56") (pinfunction "PD9_56") (pintype "passive"))
    )
    (net (code "26") (name "/C11") (class "Default")
      (node (ref "U17") (pin "57") (pinfunction "PD10_57") (pintype "passive"))
    )
    (net (code "27") (name "/C12") (class "Default")
      (node (ref "U17") (pin "58") (pinfunction "PD11_58") (pintype "passive"))
    )
    (net (code "28") (name "/C13") (class "Default")
      (node (ref "U17") (pin "59") (pinfunction "PD12_59") (pintype "passive"))
    )
    (net (code "29") (name "/CLK") (class "Default")
      (node (ref "H4") (pin "3") (pinfunction "3_3") (pintype "passive"))
      (node (ref "U17") (pin "76") (pinfunction "PA14_76") (pintype "passive"))
    )
    (net (code "30") (name "/CLK_A") (class "Default")
      (node (ref "U17") (pin "63") (pinfunction "PC6_63") (pintype "passive+no_connect"))
    )
    (net (code "31") (name "/CLK_B") (class "Default")
      (node (ref "U17") (pin "64") (pinfunction "PC7_64") (pintype "passive+no_connect"))
    )
    (net (code "32") (name "/D") (class "Default")
      (node (ref "U17") (pin "32") (pinfunction "PA7_32") (pintype "passive+no_connect"))
    )
    (net (code "33") (name "/DIO") (class "Default")
      (node (ref "H4") (pin "4") (pinfunction "4_4") (pintype "passive"))
      (node (ref "U17") (pin "72") (pinfunction "PA13_72") (pintype "passive"))
    )
    (net (code "34") (name "/E") (class "Default")
      (node (ref "U17") (pin "33") (pinfunction "PC4_33") (pintype "passive+no_connect"))
    )
    (net (code "35") (name "/F") (class "Default")
      (node (ref "U17") (pin "34") (pinfunction "PC5_34") (pintype "passive+no_connect"))
    )
    (net (code "36") (name "/FB 5V") (class "Default")
      (node (ref "R209") (pin "1") (pinfunction "1_1") (pintype "passive"))
      (node (ref "R212") (pin "2") (pinfunction "2_2") (pintype "passive"))
      (node (ref "U15") (pin "5") (pinfunction "FB_5") (pintype "passive"))
    )
    (net (code "37") (name "/FB 24V") (class "Default")
      (node (ref "C55") (pin "2") (pinfunction "2_2") (pintype "passive"))
      (node (ref "C56") (pin "2") (pinfunction "2_2") (pintype "passive"))
      (node (ref "R206") (pin "1") (pinfunction "1_1") (pintype "passive"))
      (node (ref "R207") (pin "2") (pinfunction "2_2") (pintype "passive"))
      (node (ref "R208") (pin "2") (pinfunction "2_2") (pintype "passive"))
      (node (ref "U14") (pin "5") (pinfunction "FB_5") (pintype "passive"))
    )
    (net (code "38") (name "/G") (class "Default")
      (node (ref "U17") (pin "35") (pinfunction "PB0_35") (pintype "passive+no_connect"))
    )
    (net (code "39") (name "/H") (class "Default")
      (node (ref "U17") (pin "36") (pinfunction "PB1_36") (pintype "passive+no_connect"))
    )
    (net (code "40") (name "/H1") (class "Default")
      (node (ref "U17") (pin "97") (pinfunction "PE0_97") (pintype "passive"))
    )
    (net (code "41") (name "/H2") (class "Default")
      (node (ref "U17") (pin "98") (pinfunction "PE1_98") (pintype "passive"))
    )
    (net (code "42") (name "/H3") (class "Default")
      (node (ref "U17") (pin "1") (pinfunction "PE2_1") (pintype "passive"))
    )
    (net (code "43") (name "/H4") (class "Default")
      (node (ref "U17") (pin "2") (pinfunction "PE3_2") (pintype "passive"))
    )
    (net (code "44") (name "/H5") (class "Default")
      (node (ref "U17") (pin "3") (pinfunction "PE4_3") (pintype "passive"))
    )
    (net (code "45") (name "/H6") (class "Default")
      (node (ref "U17") (pin "4") (pinfunction "PE5_4") (pintype "passive"))
    )
    (net (code "46") (name "/H7") (class "Default")
      (node (ref "U17") (pin "5") (pinfunction "PE6_5") (pintype "passive"))
    )
    (net (code "47") (name "/K1") (class "Default")
      (node (ref "H6") (pin "1") (pinfunction "1_1") (pintype "passive"))
      (node (ref "U17") (pin "41") (pinfunction "PE10_41") (pintype "passive"))
    )
    (net (code "48") (name "/K2") (class "Default")
      (node (ref "H6") (pin "2") (pinfunction "2_2") (pintype "passive"))
      (node (ref "U17") (pin "42") (pinfunction "PE11_42") (pintype "passive"))
    )
    (net (code "49") (name "/K3") (class "Default")
      (node (ref "H6") (pin "3") (pinfunction "3_3") (pintype "passive"))
      (node (ref "U17") (pin "43") (pinfunction "PE12_43") (pintype "passive"))
    )
    (net (code "50") (name "/K4") (class "Default")
      (node (ref "H6") (pin "4") (pinfunction "4_4") (pintype "passive"))
      (node (ref "U17") (pin "44") (pinfunction "PE13_44") (pintype "passive"))
    )
    (net (code "51") (name "/K5") (class "Default")
      (node (ref "H6") (pin "5") (pinfunction "5_5") (pintype "passive"))
      (node (ref "U17") (pin "45") (pinfunction "PE14_45") (pintype "passive"))
    )
    (net (code "52") (name "/K6") (class "Default")
      (node (ref "H6") (pin "6") (pinfunction "6_6") (pintype "passive"))
      (node (ref "U17") (pin "46") (pinfunction "PE15_46") (pintype "passive"))
    )
    (net (code "53") (name "/LED_PW") (class "Default")
      (node (ref "U17") (pin "17") (pinfunction "PC2_17") (pintype "passive"))
    )
    (net (code "54") (name "/LED_SET") (class "Default")
      (node (ref "U17") (pin "38") (pinfunction "PE7_38") (pintype "passive"))
    )
    (net (code "55") (name "/LED_STOP") (class "Default")
      (node (ref "U17") (pin "40") (pinfunction "PE9_40") (pintype "passive"))
    )
    (net (code "56") (name "/M0.1") (class "Default")
      (node (ref "M1") (pin "1") (pinfunction "M0_1") (pintype "passive"))
      (node (ref "U17") (pin "71") (pinfunction "PA12_71") (pintype "passive"))
    )
    (net (code "57") (name "/M0.2") (class "Default")
      (node (ref "U17") (pin "53") (pinfunction "PB14_53") (pintype "passive"))
    )
    (net (code "58") (name "/M1.1") (class "Default")
      (node (ref "M1") (pin "2") (pinfunction "M1_2") (pintype "passive"))
      (node (ref "U17") (pin "70") (pinfunction "PA11_70") (pintype "passive"))
    )
    (net (code "59") (name "/M1.2") (class "Default")
      (node (ref "U17") (pin "52") (pinfunction "PB13_52") (pintype "passive"))
    )
    (net (code "60") (name "/MCU_BT") (class "Default")
      (node (ref "R215") (pin "2") (pinfunction "2_2") (pintype "passive"))
      (node (ref "R216") (pin "2") (pinfunction "2_2") (pintype "passive"))
      (node (ref "R217") (pin "2") (pinfunction "2_2") (pintype "passive"))
      (node (ref "U17") (pin "15") (pinfunction "PC0_15") (pintype "passive"))
    )
    (net (code "61") (name "/MCU_EN") (class "Default")
      (node (ref "R221") (pin "2") (pinfunction "2_2") (pintype "passive"))
      (node (ref "U17") (pin "16") (pinfunction "PC1_16") (pintype "passive"))
    )
    (net (code "62") (name "/NRST") (class "Default")
      (node (ref "R223") (pin "2") (pinfunction "2_2") (pintype "passive"))
      (node (ref "SW1") (pin "1") (pinfunction "1_1") (pintype "passive"))
      (node (ref "U17") (pin "14") (pinfunction "NRST_14") (pintype "passive"))
    )
    (net (code "63") (name "/PA0") (class "Default")
      (node (ref "U17") (pin "23") (pinfunction "PA0_23") (pintype "passive+no_connect"))
    )
    (net (code "64") (name "/PA1") (class "Default")
      (node (ref "U17") (pin "24") (pinfunction "PA1_24") (pintype "passive+no_connect"))
    )
    (net (code "65") (name "/PA2") (class "Default")
      (node (ref "H7") (pin "3") (pinfunction "3_3") (pintype "passive"))
      (node (ref "U17") (pin "25") (pinfunction "PA2_25") (pintype "passive"))
    )
    (net (code "66") (name "/PA3") (class "Default")
      (node (ref "H7") (pin "2") (pinfunction "2_2") (pintype "passive"))
      (node (ref "U17") (pin "26") (pinfunction "PA3_26") (pintype "passive"))
    )
    (net (code "67") (name "/PA9") (class "Default")
      (node (ref "M1") (pin "3") (pinfunction "RXD_3") (pintype "passive"))
      (node (ref "U17") (pin "68") (pinfunction "PA9_68") (pintype "passive"))
    )
    (net (code "68") (name "/PA10") (class "Default")
      (node (ref "M1") (pin "4") (pinfunction "TXD_4") (pintype "passive"))
      (node (ref "U17") (pin "69") (pinfunction "PA10_69") (pintype "passive"))
    )
    (net (code "71") (name "/PB2") (class "Default")
      (node (ref "U17") (pin "37") (pinfunction "PB2_37") (pintype "passive"))
    )
    (net (code "72") (name "/PB3") (class "Default")
      (node (ref "U17") (pin "89") (pinfunction "PB3_89") (pintype "passive"))
    )
    (net (code "73") (name "/PB4") (class "Default")
      (node (ref "U17") (pin "90") (pinfunction "PB4_90") (pintype "passive"))
    )
    (net (code "74") (name "/PB5") (class "Default")
      (node (ref "U17") (pin "91") (pinfunction "PB5_91") (pintype "passive"))
    )
    (net (code "75") (name "/PB6") (class "Default")
      (node (ref "U17") (pin "92") (pinfunction "PB6_92") (pintype "passive"))
    )
    (net (code "76") (name "/PB7") (class "Default")
      (node (ref "U17") (pin "93") (pinfunction "PB7_93") (pintype "passive"))
    )
    (net (code "77") (name "/PB8") (class "Default")
      (node (ref "U17") (pin "95") (pinfunction "PB8_95") (pintype "passive"))
    )
    (net (code "78") (name "/PB9") (class "Default")
      (node (ref "U17") (pin "96") (pinfunction "PB9_96") (pintype "passive"))
    )
    (net (code "79") (name "/PB10") (class "Default")
      (node (ref "U17") (pin "47") (pinfunction "PB10_47") (pintype "passive+no_connect"))
    )
    (net (code "80") (name "/PB11") (class "Default")
      (node (ref "U17") (pin "48") (pinfunction "PB11_48") (pintype "passive+no_connect"))
    )
    (net (code "81") (name "/PB15") (class "Default")
      (node (ref "U17") (pin "54") (pinfunction "PB15_54") (pintype "passive"))
    )
    (net (code "82") (name "/PC8") (class "Default")
      (node (ref "U17") (pin "65") (pinfunction "PC8_65") (pintype "passive+no_connect"))
    )
    (net (code "83") (name "/PC9") (class "Default")
      (node (ref "U17") (pin "66") (pinfunction "PC9_66") (pintype "passive+no_connect"))
    )
    (net (code "84") (name "/PC13") (class "Default")
      (node (ref "U17") (pin "7") (pinfunction "PC13_7") (pintype "passive+no_connect"))
    )
    (net (code "85") (name "/PC14") (class "Default")
      (node (ref "U17") (pin "8") (pinfunction "PC14_8") (pintype "passive+no_connect"))
    )
    (net (code "86") (name "/PC15") (class "Default")
      (node (ref "U17") (pin "9") (pinfunction "PC15_9") (pintype "passive+no_connect"))
    )
    (net (code "87") (name "/PD13") (class "Default")
      (node (ref "U17") (pin "60") (pinfunction "PD13_60") (pintype "passive+no_connect"))
    )
    (net (code "88") (name "/PD14") (class "Default")
      (node (ref "U17") (pin "61") (pinfunction "PD14_61") (pintype "passive+no_connect"))
    )
    (net (code "89") (name "/PD15") (class "Default")
      (node (ref "U17") (pin "62") (pinfunction "PD15_62") (pintype "passive+no_connect"))
    )
    (net (code "90") (name "/PE8") (class "Default")
      (node (ref "U17") (pin "39") (pinfunction "PE8_39") (pintype "passive"))
    )
    (net (code "91") (name "/PH0") (class "Default")
      (node (ref "C81") (pin "1") (pinfunction "1_1") (pintype "passive"))
      (node (ref "U17") (pin "12") (pinfunction "PH0_12") (pintype "passive"))
      (node (ref "X1") (pin "3") (pinfunction "3_3") (pintype "passive"))
    )
    (net (code "92") (name "/PH1") (class "Default")
      (node (ref "C90") (pin "1") (pinfunction "1_1") (pintype "passive"))
      (node (ref "U17") (pin "13") (pinfunction "PH1_13") (pintype "passive"))
      (node (ref "X1") (pin "1") (pinfunction "1_1") (pintype "passive"))
    )
    (net (code "93") (name "BAT+") (class "Default")
      (node (ref "C78") (pin "2") (pinfunction "2_2") (pintype "passive"))
      (node (ref "H5") (pin "1") (pinfunction "1_1") (pintype "passive"))
      (node (ref "Q94") (pin "3") (pinfunction "S_3") (pintype "passive"))
      (node (ref "R219") (pin "2") (pinfunction "2_2") (pintype "passive"))
    )
    (net (code "94") (name "BAT_EN") (class "Default")
      (node (ref "C43") (pin "1") (pinfunction "1_1") (pintype "passive"))
      (node (ref "C48") (pin "2") (pinfunction "2_2") (pintype "passive"))
      (node (ref "C49") (pin "2") (pinfunction "2_2") (pintype "passive"))
      (node (ref "C50") (pin "1") (pinfunction "1_1") (pintype "passive"))
      (node (ref "C52") (pin "2") (pinfunction "2_2") (pintype "passive"))
      (node (ref "C63") (pin "1") (pinfunction "1_1") (pintype "passive"))
      (node (ref "C64") (pin "1") (pinfunction "1_1") (pintype "passive"))
      (node (ref "C71") (pin "1") (pinfunction "1_1") (pintype "passive"))
      (node (ref "C72") (pin "2") (pinfunction "2_2") (pintype "passive"))
      (node (ref "L1") (pin "1") (pinfunction "1_1") (pintype "passive"))
      (node (ref "Q94") (pin "2") (pinfunction "D_2") (pintype "passive"))
      (node (ref "R201") (pin "1") (pinfunction "1_1") (pintype "passive"))
      (node (ref "R214") (pin "2") (pinfunction "2_2") (pintype "passive"))
      (node (ref "U14") (pin "10") (pinfunction "VDD_10") (pintype "passive"))
      (node (ref "U15") (pin "2") (pinfunction "VIN_2") (pintype "passive"))
    )
    (net (code "95") (name "GND") (class "Default")
      (node (ref "C43") (pin "2") (pinfunction "2_2") (pintype "passive"))
      (node (ref "C44") (pin "1") (pinfunction "1_1") (pintype "passive"))
      (node (ref "C45") (pin "1") (pinfunction "1_1") (pintype "passive"))
      (node (ref "C48") (pin "1") (pinfunction "1_1") (pintype "passive"))
      (node (ref "C49") (pin "1") (pinfunction "1_1") (pintype "passive"))
      (node (ref "C50") (pin "2") (pinfunction "2_2") (pintype "passive"))
      (node (ref "C51") (pin "1") (pinfunction "1_1") (pintype "passive"))
      (node (ref "C52") (pin "1") (pinfunction "1_1") (pintype "passive"))
      (node (ref "C53") (pin "2") (pinfunction "2_2") (pintype "passive"))
      (node (ref "C54") (pin "1") (pinfunction "1_1") (pintype "passive"))
      (node (ref "C58") (pin "1") (pinfunction "1_1") (pintype "passive"))
      (node (ref "C59") (pin "1") (pinfunction "1_1") (pintype "passive"))
      (node (ref "C60") (pin "2") (pinfunction "2_2") (pintype "passive"))
      (node (ref "C62") (pin "1") (pinfunction "1_1") (pintype "passive"))
      (node (ref "C63") (pin "2") (pinfunction "2_2") (pintype "passive"))
      (node (ref "C64") (pin "2") (pinfunction "2_2") (pintype "passive"))
      (node (ref "C65") (pin "1") (pinfunction "1_1") (pintype "passive"))
      (node (ref "C66") (pin "1") (pinfunction "1_1") (pintype "passive"))
      (node (ref "C67") (pin "1") (pinfunction "1_1") (pintype "passive"))
      (node (ref "C68") (pin "2") (pinfunction "2_2") (pintype "passive"))
      (node (ref "C69") (pin "1") (pinfunction "1_1") (pintype "passive"))
      (node (ref "C70") (pin "1") (pinfunction "1_1") (pintype "passive"))
      (node (ref "C71") (pin "2") (pinfunction "2_2") (pintype "passive"))
      (node (ref "C72") (pin "1") (pinfunction "1_1") (pintype "passive"))
      (node (ref "C73") (pin "2") (pinfunction "2_2") (pintype "passive"))
      (node (ref "C74") (pin "1") (pinfunction "1_1") (pintype "passive"))
      (node (ref "C75") (pin "1") (pinfunction "1_1") (pintype "passive"))
      (node (ref "C76") (pin "2") (pinfunction "2_2") (pintype "passive"))
      (node (ref "C77") (pin "2") (pinfunction "2_2") (pintype "passive"))
      (node (ref "D2") (pin "1") (pinfunction "Anode_1") (pintype "passive"))
      (node (ref "H4") (pin "2") (pinfunction "2_2") (pintype "passive"))
      (node (ref "H5") (pin "2") (pinfunction "2_2") (pintype "passive"))
      (node (ref "H7") (pin "1") (pinfunction "1_1") (pintype "passive"))
      (node (ref "M1") (pin "7") (pinfunction "GND_7") (pintype "passive"))
      (node (ref "Q93") (pin "2") (pinfunction "E_2") (pintype "passive"))
      (node (ref "Q95") (pin "2") (pinfunction "E_2") (pintype "passive"))
      (node (ref "R205") (pin "1") (pinfunction "1_1") (pintype "passive"))
      (node (ref "R208") (pin "1") (pinfunction "1_1") (pintype "passive"))
      (node (ref "R211") (pin "1") (pinfunction "1_1") (pintype "passive"))
      (node (ref "R212") (pin "1") (pinfunction "1_1") (pintype "passive"))
      (node (ref "R213") (pin "2") (pinfunction "2_2") (pintype "passive"))
      (node (ref "R217") (pin "1") (pinfunction "1_1") (pintype "passive"))
      (node (ref "R218") (pin "1") (pinfunction "1_1") (pintype "passive"))
      (node (ref "R222") (pin "1") (pinfunction "1_1") (pintype "passive"))
      (node (ref "R225") (pin "1") (pinfunction "1_1") (pintype "passive"))
      (node (ref "RSNS1") (pin "1") (pinfunction "1_1") (pintype "passive"))
      (node (ref "U14") (pin "11") (pinfunction "EP_11") (pintype "passive"))
      (node (ref "U14") (pin "3") (pinfunction "DIS_3") (pintype "passive"))
      (node (ref "U14") (pin "6") (pinfunction "GND_6") (pintype "passive"))
      (node (ref "U15") (pin "0") (pinfunction "GND_0") (pintype "passive"))
      (node (ref "U15") (pin "7") (pinfunction "GND_7") (pintype "passive"))
      (node (ref "U16") (pin "1") (pinfunction "GND_1") (pintype "passive"))
    )
    (net (code "96") (name "GND_MCU") (class "Default")
      (node (ref "C79") (pin "1") (pinfunction "1_1") (pintype "passive"))
      (node (ref "C80") (pin "1") (pinfunction "1_1") (pintype "passive"))
      (node (ref "C81") (pin "2") (pinfunction "2_2") (pintype "passive"))
      (node (ref "C82") (pin "1") (pinfunction "1_1") (pintype "passive"))
      (node (ref "C83") (pin "1") (pinfunction "1_1") (pintype "passive"))
      (node (ref "C84") (pin "1") (pinfunction "1_1") (pintype "passive"))
      (node (ref "C85") (pin "1") (pinfunction "1_1") (pintype "passive"))
      (node (ref "C86") (pin "1") (pinfunction "1_1") (pintype "passive"))
      (node (ref "C87") (pin "2") (pinfunction "2_2") (pintype "passive"))
      (node (ref "C88") (pin "1") (pinfunction "1_1") (pintype "passive"))
      (node (ref "C89") (pin "1") (pinfunction "1_1") (pintype "passive"))
      (node (ref "C90") (pin "2") (pinfunction "2_2") (pintype "passive"))
      (node (ref "R224") (pin "1") (pinfunction "1_1") (pintype "passive"))
      (node (ref "R225") (pin "2") (pinfunction "2_2") (pintype "passive"))
      (node (ref "SW1") (pin "2") (pinfunction "2_2") (pintype "passive"))
      (node (ref "U17") (pin "10") (pinfunction "VSS_10") (pintype "passive"))
      (node (ref "U17") (pin "20") (pinfunction "VSSA_20") (pintype "passive"))
      (node (ref "U17") (pin "27") (pinfunction "VSS_27") (pintype "passive"))
      (node (ref "U17") (pin "74") (pinfunction "VSS_74") (pintype "passive"))
      (node (ref "U17") (pin "99") (pinfunction "VSS_99") (pintype "passive"))
      (node (ref "X1") (pin "2") (pinfunction "2_2") (pintype "passive"))
      (node (ref "X1") (pin "4") (pinfunction "4_4") (pintype "passive"))
    )
    (net (code "97") (name "Net-(C46-Pad2)") (class "Default")
      (node (ref "C46") (pin "2") (pinfunction "2_2") (pintype "passive"))
      (node (ref "C47") (pin "2") (pinfunction "2_2") (pintype "passive"))
      (node (ref "R205") (pin "2") (pinfunction "2_2") (pintype "passive"))
    )
    (net (code "98") (name "Net-(C57-Pad2)") (class "Default")
      (node (ref "C57") (pin "2") (pinfunction "2_2") (pintype "passive"))
      (node (ref "R207") (pin "1") (pinfunction "1_1") (pintype "passive"))
    )
    (net (code "99") (name "Net-(C70-Pad2)") (class "Default")
      (node (ref "C70") (pin "2") (pinfunction "2_2") (pintype "passive"))
      (node (ref "R210") (pin "2") (pinfunction "2_2") (pintype "passive"))
    )
    (net (code "100") (name "Net-(C75-Pad2)") (class "Default")
      (node (ref "C75") (pin "2") (pinfunction "2_2") (pintype "passive"))
      (node (ref "C76") (pin "1") (pinfunction "1_1") (pintype "passive"))
      (node (ref "F1") (pin "1") (pinfunction "1_1") (pintype "passive"))
      (node (ref "U16") (pin "2") (pinfunction "VOUT_2") (pintype "passive"))
      (node (ref "U16") (pin "4") (pinfunction "VOUT_4") (pintype "passive"))
    )
    (net (code "101") (name "Net-(D1-Anode)") (class "Default")
      (node (ref "D1") (pin "1") (pinfunction "Anode_1") (pintype "passive"))
      (node (ref "L1") (pin "2") (pinfunction "2_2") (pintype "passive"))
      (node (ref "Q92") (pin "5") (pinfunction "D_5") (pintype "passive"))
      (node (ref "Q92") (pin "6") (pinfunction "D_6") (pintype "passive"))
      (node (ref "Q92") (pin "7") (pinfunction "D_7") (pintype "passive"))
      (node (ref "Q92") (pin "8") (pinfunction "D_8") (pintype "passive"))
      (node (ref "Q92") (pin "TAB") (pinfunction "D_TAB") (pintype "passive"))
    )
    (net (code "102") (name "Net-(D2-Kathode)") (class "Default")
      (node (ref "C61") (pin "1") (pinfunction "1_1") (pintype "passive"))
      (node (ref "D2") (pin "2") (pinfunction "Kathode_2") (pintype "passive"))
      (node (ref "L2") (pin "1") (pinfunction "1_1") (pintype "passive"))
      (node (ref "U15") (pin "8") (pinfunction "SW_8") (pintype "passive"))
    )
    (net (code "103") (name "Net-(Q92-G)") (class "Default")
      (node (ref "Q92") (pin "4") (pinfunction "G_4") (pintype "passive"))
      (node (ref "R203") (pin "2") (pinfunction "2_2") (pintype "passive"))
    )
    (net (code "104") (name "Net-(Q92-S-Pad1)") (class "Default")
      (node (ref "Q92") (pin "1") (pinfunction "S_1") (pintype "passive"))
      (node (ref "Q92") (pin "2") (pinfunction "S_2") (pintype "passive"))
      (node (ref "Q92") (pin "3") (pinfunction "S_3") (pintype "passive"))
      (node (ref "R204") (pin "2") (pinfunction "2_2") (pintype "passive"))
      (node (ref "RSNS1") (pin "2") (pinfunction "2_2") (pintype "passive"))
    )
    (net (code "105") (name "Net-(Q93-B)") (class "Default")
      (node (ref "Q93") (pin "1") (pinfunction "B_1") (pintype "passive"))
      (node (ref "R216") (pin "1") (pinfunction "1_1") (pintype "passive"))
      (node (ref "R218") (pin "2") (pinfunction "2_2") (pintype "passive"))
    )
    (net (code "106") (name "Net-(Q93-C)") (class "Default")
      (node (ref "C78") (pin "1") (pinfunction "1_1") (pintype "passive"))
      (node (ref "Q93") (pin "3") (pinfunction "C_3") (pintype "passive"))
      (node (ref "Q95") (pin "3") (pinfunction "C_3") (pintype "passive"))
      (node (ref "R219") (pin "1") (pinfunction "1_1") (pintype "passive"))
      (node (ref "R220") (pin "2") (pinfunction "2_2") (pintype "passive"))
    )
    (net (code "107") (name "Net-(Q94-G)") (class "Default")
      (node (ref "Q94") (pin "1") (pinfunction "G_1") (pintype "passive"))
      (node (ref "R220") (pin "1") (pinfunction "1_1") (pintype "passive"))
    )
    (net (code "108") (name "Net-(Q95-B)") (class "Default")
      (node (ref "Q95") (pin "1") (pinfunction "B_1") (pintype "passive"))
      (node (ref "R221") (pin "1") (pinfunction "1_1") (pintype "passive"))
      (node (ref "R222") (pin "2") (pinfunction "2_2") (pintype "passive"))
    )
    (net (code "109") (name "Net-(R201-Pad2)") (class "Default")
      (node (ref "R201") (pin "2") (pinfunction "2_2") (pintype "passive"))
      (node (ref "R202") (pin "1") (pinfunction "1_1") (pintype "passive"))
    )
    (net (code "110") (name "Net-(U14-BP)") (class "Default")
      (node (ref "C53") (pin "1") (pinfunction "1_1") (pintype "passive"))
      (node (ref "U14") (pin "9") (pinfunction "BP_9") (pintype "passive"))
    )
    (net (code "111") (name "Net-(U14-COMP)") (class "Default")
      (node (ref "C55") (pin "1") (pinfunction "1_1") (pintype "passive"))
      (node (ref "C56") (pin "1") (pinfunction "1_1") (pintype "passive"))
      (node (ref "C57") (pin "1") (pinfunction "1_1") (pintype "passive"))
      (node (ref "U14") (pin "4") (pinfunction "COMP_4") (pintype "passive"))
    )
    (net (code "112") (name "Net-(U14-GDRV)") (class "Default")
      (node (ref "R203") (pin "1") (pinfunction "1_1") (pintype "passive"))
      (node (ref "U14") (pin "8") (pinfunction "GDRV_8") (pintype "passive"))
    )
    (net (code "113") (name "Net-(U14-ISNS)") (class "Default")
      (node (ref "C54") (pin "2") (pinfunction "2_2") (pintype "passive"))
      (node (ref "R204") (pin "1") (pinfunction "1_1") (pintype "passive"))
      (node (ref "U14") (pin "7") (pinfunction "ISNS_7") (pintype "passive"))
    )
    (net (code "114") (name "Net-(U14-RC)") (class "Default")
      (node (ref "C51") (pin "2") (pinfunction "2_2") (pintype "passive"))
      (node (ref "R202") (pin "2") (pinfunction "2_2") (pintype "passive"))
      (node (ref "U14") (pin "1") (pinfunction "RC_1") (pintype "passive"))
    )
    (net (code "115") (name "Net-(U14-SS)") (class "Default")
      (node (ref "C46") (pin "1") (pinfunction "1_1") (pintype "passive"))
      (node (ref "C47") (pin "1") (pinfunction "1_1") (pintype "passive"))
      (node (ref "U14") (pin "2") (pinfunction "SS_2") (pintype "passive"))
    )
    (net (code "116") (name "Net-(U15-BOOT)") (class "Default")
      (node (ref "C61") (pin "2") (pinfunction "2_2") (pintype "passive"))
      (node (ref "U15") (pin "1") (pinfunction "BOOT_1") (pintype "passive"))
    )
    (net (code "117") (name "Net-(U15-CLK)") (class "Default")
      (node (ref "R211") (pin "2") (pinfunction "2_2") (pintype "passive"))
      (node (ref "U15") (pin "4") (pinfunction "CLK_4") (pintype "passive"))
    )
    (net (code "118") (name "Net-(U15-COMP)") (class "Default")
      (node (ref "C62") (pin "2") (pinfunction "2_2") (pintype "passive"))
      (node (ref "R210") (pin "1") (pinfunction "1_1") (pintype "passive"))
      (node (ref "U15") (pin "6") (pinfunction "COMP_6") (pintype "passive"))
    )
    (net (code "119") (name "Net-(U17-VCAP_1)") (class "Default")
      (node (ref "C88") (pin "2") (pinfunction "2_2") (pintype "passive"))
      (node (ref "C89") (pin "2") (pinfunction "2_2") (pintype "passive"))
      (node (ref "U17") (pin "49") (pinfunction "VCAP_1_49") (pintype "passive"))
    )
    (net (code "120") (name "Net-(U17-VCAP_2)") (class "Default")
      (node (ref "C79") (pin "2") (pinfunction "2_2") (pintype "passive"))
      (node (ref "C80") (pin "2") (pinfunction "2_2") (pintype "passive"))
      (node (ref "U17") (pin "73") (pinfunction "VCAP_2_73") (pintype "passive"))
    )
    (net (code "121") (name "unconnected-(U15-EN-Pad3)") (class "Default")
      (node (ref "U15") (pin "3") (pinfunction "EN_3") (pintype "passive+no_connect"))
    )
    (net (code "122") (name "unconnected-(U17-VREF+-Pad21)") (class "Default")
      (node (ref "U17") (pin "21") (pinfunction "VREF+_21") (pintype "passive"))
    )
  )
)
